# Brake_SCH.net
KiCad netlist of a schematic drawn in Altium Designer
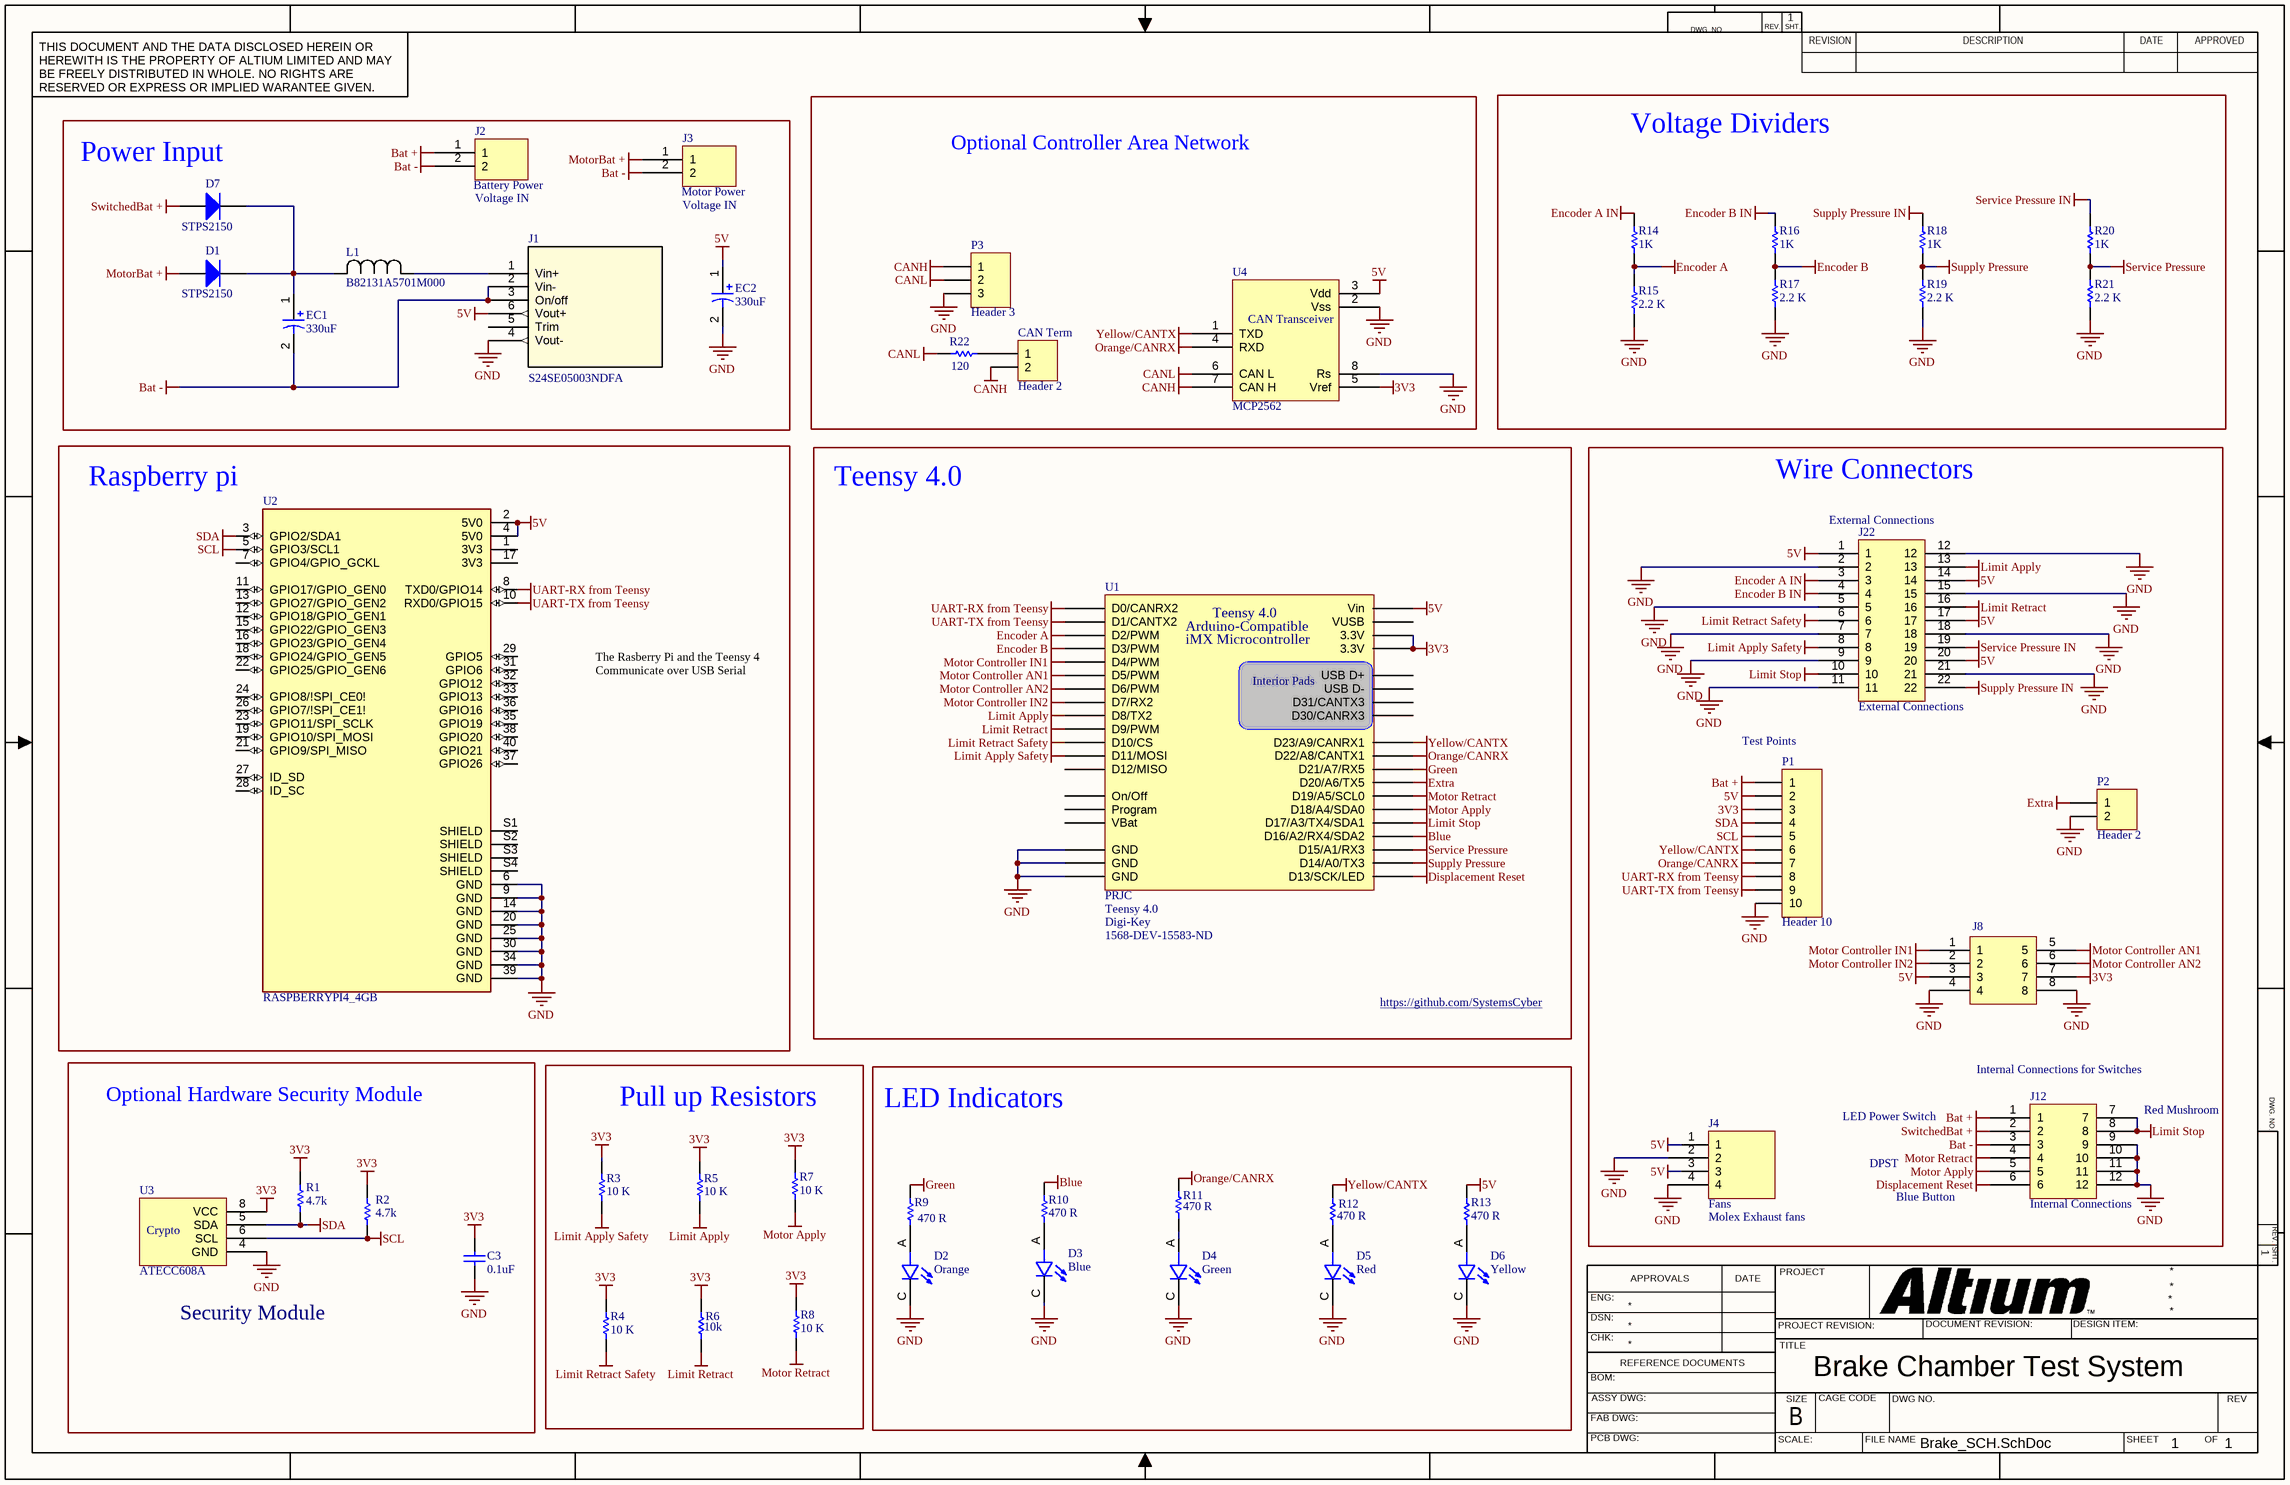
[diagram p0: Brake_SCH.SchDoc]

(export (version "E")
  (design (tool "Eeschema 10.0.6"))
  (components
    (comp (ref "C3")
      (value "0.1uF")
      (footprint "CAPR5-4X5")
      (description "Capacitor")
      (libsource (lib "Miscellaneous Devices") (part "Cap"))
    )
    (comp (ref "CAN Term")
      (value "Header 2")
      (footprint "HDR1X2")
      (description "Header, 2-Pin")
      (fields (field (name "PUBLISHER") "Altium Limited"))
      (libsource (lib "Miscellaneous Connectors") (part "Header 2"))
    )
    (comp (ref "D1")
      (value "STPS2150")
      (footprint "DO-201AD")
      (description "DIODE SCHOTTKY 150V 2A DO15")
      (libsource (lib "Miscellaneous Devices") (part "Diode 1N5408"))
    )
    (comp (ref "D2")
      (value "Orange")
      (footprint "LED_151054RS03000")
      (description "Red 623nm LED Indication - Discrete 1.9V Radial")
      (libsource (lib "151054RS03000") (part "151054RS03000"))
    )
    (comp (ref "D3")
      (value "Blue")
      (footprint "LED_151054RS03000")
      (description "Red 623nm LED Indication - Discrete 1.9V Radial")
      (libsource (lib "151054RS03000") (part "151054RS03000"))
    )
    (comp (ref "D4")
      (value "Green")
      (footprint "LED_151054RS03000")
      (description "Red 623nm LED Indication - Discrete 1.9V Radial")
      (libsource (lib "151054RS03000") (part "151054RS03000"))
    )
    (comp (ref "D5")
      (value "Red")
      (footprint "LED_151054RS03000")
      (description "Red 623nm LED Indication - Discrete 1.9V Radial")
      (libsource (lib "151054RS03000") (part "151054RS03000"))
    )
    (comp (ref "D6")
      (value "Yellow")
      (footprint "LED_151054RS03000")
      (description "Red 623nm LED Indication - Discrete 1.9V Radial")
      (libsource (lib "151054RS03000") (part "151054RS03000"))
    )
    (comp (ref "D7")
      (value "STPS2150")
      (footprint "DO-201AD")
      (description "DIODE SCHOTTKY 150V 2A DO15")
      (libsource (lib "Miscellaneous Devices") (part "Diode 1N5408"))
    )
    (comp (ref "EC1")
      (value "330uF")
      (footprint "Cap - 15mm Polarized")
      (description "CAP ALUM 220UF 20% 100V RADIAL")
      (fields (field (name "MANUFACTURER") "Nichicon") (field (name "PARTNUMBER") "UBT2A221MHD1TN"))
      (libsource (lib "Custom Parts") (part "Capacitor, Polarized"))
    )
    (comp (ref "EC2")
      (value "330uF")
      (footprint "Cap - 15mm Polarized")
      (description "CAP ALUM 220UF 20% 100V RADIAL")
      (fields (field (name "MANUFACTURER") "Nichicon") (field (name "PARTNUMBER") "UBT2A221MHD1TN"))
      (libsource (lib "Custom Parts") (part "Capacitor, Polarized"))
    )
    (comp (ref "J1")
      (value "S24SE05003NDFA")
      (footprint "CONN6_3NDFA_DEA")
      (description "No Description Available")
      (libsource (lib "S24SE05003NDFA") (part "S24SE05003NDFA"))
    )
    (comp (ref "J2")
      (value "Battery Power")
      (footprint "2 pos Mini-Fit Jr. R/A Header")
      (fields (field (name "PARTNUMBER") "39-30-1020") (field (name "MANUFACTURER") "Voltage IN"))
      (libsource (lib "Molex Mini-Fit Jr") (part "2 Pos Header"))
    )
    (comp (ref "J3")
      (value "Motor Power")
      (footprint "2 pos Mini-Fit Jr. R/A Header")
      (fields (field (name "PARTNUMBER") "39-30-1020") (field (name "MANUFACTURER") "Voltage IN"))
      (libsource (lib "Molex Mini-Fit Jr") (part "2 Pos Header"))
    )
    (comp (ref "J4")
      (value "Fans")
      (footprint "4 POS MINI-FIT JR")
      (description "CONN HEADER 4POS 4.2MM VERT TIN")
      (fields (field (name "PARTNUMBER") "39-29-9040") (field (name "MANUFACTURER") "Molex Exhaust fans"))
      (libsource (lib "Molex Mini-Fit Jr") (part "4 Pos Header Vert"))
    )
    (comp (ref "J8")
      (value "Motor Controller")
      (footprint "8 pos Mini-Fit Jr. R/A Header")
      (description "CONN HEADER 8POS 4.2MM R/A TIN")
      (fields (field (name "PARTNUMBER") "39-30-1080") (field (name "MANUFACTURER") "Molex"))
      (libsource (lib "Molex Mini-Fit Jr") (part "8 Pos Header"))
    )
    (comp (ref "J12")
      (value "Internal Connections")
      (footprint "12 pos Mini-Fit Jr. R/A Header")
      (fields (field (name "MANUFACTURER") "Molex") (field (name "PARTNUMBER") "39-30-1120"))
      (libsource (lib "Molex Mini-Fit Jr") (part "12 Pos Header"))
    )
    (comp (ref "J22")
      (value "External Connections")
      (footprint "22 pos Mini-Fit Jr. R/A Header")
      (fields (field (name "MANUFACTURER") "Molex") (field (name "PARTNUMBER") "39-30-1220"))
      (libsource (lib "Molex Mini-Fit Jr") (part "22 Pos Header"))
    )
    (comp (ref "L1")
      (value "B82131A5701M000")
      (footprint "AXIAL-0.8")
      (description "14 µH Unshielded Drum Core, Wirewound Inductor 700 mA 760mOhm Axial")
      (fields (field (name "PARTNUMBER") "8230-20-RC"))
      (libsource (lib "8230-20-RC") (part "8230-20-RC"))
    )
    (comp (ref "P1")
      (value "Header 10")
      (footprint "HDR1X10")
      (description "Header, 10-Pin")
      (fields (field (name "PUBLISHER") "Altium Limited"))
      (libsource (lib "Miscellaneous Connectors") (part "Header 10"))
    )
    (comp (ref "P2")
      (value "Header 2")
      (footprint "HDR1X2")
      (description "Header, 2-Pin")
      (libsource (lib "Miscellaneous Connectors") (part "Header 2"))
    )
    (comp (ref "P3")
      (value "Header 3")
      (footprint "HDR1X3")
      (description "Header, 3-Pin")
      (fields (field (name "PUBLISHER") "Altium Limited"))
      (libsource (lib "Miscellaneous Connectors") (part "Header 3"))
    )
    (comp (ref "R1")
      (value "4.7k")
      (footprint "AXIAL-0.4")
      (description "Resistor")
      (libsource (lib "Miscellaneous Devices") (part "Res1"))
    )
    (comp (ref "R2")
      (value "4.7k")
      (footprint "AXIAL-0.4")
      (description "Resistor")
      (libsource (lib "Miscellaneous Devices") (part "Res1"))
    )
    (comp (ref "R3")
      (value "10 K")
      (footprint "AXIAL-0.4")
      (description "Resistor")
      (fields (field (name "Comment") "10k"))
      (libsource (lib "Miscellaneous Devices") (part "Res1"))
    )
    (comp (ref "R4")
      (value "10 K")
      (footprint "AXIAL-0.4")
      (description "Resistor")
      (fields (field (name "Comment") "10k"))
      (libsource (lib "Miscellaneous Devices") (part "Res1"))
    )
    (comp (ref "R5")
      (value "10 K")
      (footprint "AXIAL-0.4")
      (description "Resistor")
      (fields (field (name "Comment") "10k"))
      (libsource (lib "Miscellaneous Devices") (part "Res1"))
    )
    (comp (ref "R6")
      (value "10k")
      (footprint "AXIAL-0.4")
      (description "Resistor")
      (libsource (lib "Miscellaneous Devices") (part "Res1"))
    )
    (comp (ref "R7")
      (value "10 K")
      (footprint "AXIAL-0.4")
      (description "Resistor")
      (fields (field (name "Comment") "10k"))
      (libsource (lib "Miscellaneous Devices") (part "Res1"))
    )
    (comp (ref "R8")
      (value "10 K")
      (footprint "AXIAL-0.4")
      (description "Resistor")
      (fields (field (name "Comment") "10k"))
      (libsource (lib "Miscellaneous Devices") (part "Res1"))
    )
    (comp (ref "R9")
      (value "470 R")
      (footprint "AXIAL-0.4")
      (description "Resistor")
      (fields (field (name "Comment") "470"))
      (libsource (lib "Miscellaneous Devices") (part "Res1"))
    )
    (comp (ref "R10")
      (value "470 R")
      (footprint "AXIAL-0.4")
      (description "Resistor")
      (fields (field (name "Comment") "470"))
      (libsource (lib "Miscellaneous Devices") (part "Res1"))
    )
    (comp (ref "R11")
      (value "470 R")
      (footprint "AXIAL-0.4")
      (description "Resistor")
      (fields (field (name "Comment") "470"))
      (libsource (lib "Miscellaneous Devices") (part "Res1"))
    )
    (comp (ref "R12")
      (value "470 R")
      (footprint "AXIAL-0.4")
      (description "Resistor")
      (fields (field (name "Comment") "470"))
      (libsource (lib "Miscellaneous Devices") (part "Res1"))
    )
    (comp (ref "R13")
      (value "470 R")
      (footprint "AXIAL-0.4")
      (description "Resistor")
      (fields (field (name "Comment") "470"))
      (libsource (lib "Miscellaneous Devices") (part "Res1"))
    )
    (comp (ref "R14")
      (value "1K")
      (footprint "AXIAL-0.4")
      (description "Resistor")
      (fields (field (name "Comment") "1k"))
      (libsource (lib "Miscellaneous Devices") (part "Res1"))
    )
    (comp (ref "R15")
      (value "2.2 K")
      (footprint "AXIAL-0.4")
      (description "Resistor")
      (fields (field (name "Comment") "2.2k"))
      (libsource (lib "Miscellaneous Devices") (part "Res1"))
    )
    (comp (ref "R16")
      (value "1K")
      (footprint "AXIAL-0.4")
      (description "Resistor")
      (fields (field (name "Comment") "1k"))
      (libsource (lib "Miscellaneous Devices") (part "Res1"))
    )
    (comp (ref "R17")
      (value "2.2 K")
      (footprint "AXIAL-0.4")
      (description "Resistor")
      (fields (field (name "Comment") "2.2k"))
      (libsource (lib "Miscellaneous Devices") (part "Res1"))
    )
    (comp (ref "R18")
      (value "1K")
      (footprint "AXIAL-0.4")
      (description "Resistor")
      (fields (field (name "Comment") "1k"))
      (libsource (lib "Miscellaneous Devices") (part "Res1"))
    )
    (comp (ref "R19")
      (value "2.2 K")
      (footprint "AXIAL-0.4")
      (description "Resistor")
      (fields (field (name "Comment") "2.2k"))
      (libsource (lib "Miscellaneous Devices") (part "Res1"))
    )
    (comp (ref "R20")
      (value "1K")
      (footprint "AXIAL-0.4")
      (description "Resistor")
      (fields (field (name "Comment") "1k"))
      (libsource (lib "Miscellaneous Devices") (part "Res1"))
    )
    (comp (ref "R21")
      (value "2.2 K")
      (footprint "AXIAL-0.4")
      (description "Resistor")
      (fields (field (name "Comment") "2.2k"))
      (libsource (lib "Miscellaneous Devices") (part "Res1"))
    )
    (comp (ref "R22")
      (value "120")
      (footprint "AXIAL-0.4")
      (description "Resistor")
      (libsource (lib "Miscellaneous Devices") (part "Res1"))
    )
    (comp (ref "U1")
      (value "Teensy 4.0")
      (footprint "Teensy 4.0")
      (description "32 Bit Arduino-Compatible iMX Microcontroller")
      (fields
        (field (name "MANUFACTURER") "PRJC")
        (field (name "PARTNUMBER") "Teensy 4.0")
        (field (name "SUPPLIER 1") "Digi-Key")
        (field (name "SUPPLIER PART NUMBER 1") "1568-DEV-15583-ND")
      )
      (libsource (lib "Teensy") (part "Teensy_4.0"))
    )
    (comp (ref "U2")
      (value "RASPBERRYPI4_4GB")
      (footprint "Mirrored MODULE_RASPBERRY_PI_3_MODEL_B")
      (description "BCM2711 Raspberry Pi 4 Model B 4GB - ARMÂ® CortexÂ®-A72 MPU Embedded Evaluation Board")
      (libsource (lib "RASPBERRYPI4_4GB") (part "RASPBERRYPI4_4GB"))
    )
    (comp (ref "U3")
      (value "ATECC608A")
      (footprint "SOIC-8")
      (description "Authentication Chip IC Networking and Communications 8-SOIC")
      (fields
        (field (name "MANUFACTURER") "Microchip Technology")
        (field (name "PARTNUMBER") "ATECC508A-SSHDA-T")
      )
      (libsource (lib "Custom Parts") (part "ATECC508A"))
    )
    (comp (ref "U4")
      (value "MCP2562")
      (footprint "DIP8")
      (libsource (lib "SSS Integrated Library") (part "MCP2551"))
    )
  )
  (nets
    (net (code "1") (name "3V3") (class "Default")
      (node (ref "C3") (pin "2") (pinfunction "2_2") (pintype "passive"))
      (node (ref "J8") (pin "7") (pinfunction "7_7") (pintype "passive"))
      (node (ref "P1") (pin "3") (pinfunction "3_3") (pintype "passive"))
      (node (ref "R1") (pin "2") (pinfunction "2_2") (pintype "passive"))
      (node (ref "R2") (pin "2") (pinfunction "2_2") (pintype "passive"))
      (node (ref "R3") (pin "2") (pinfunction "2_2") (pintype "passive"))
      (node (ref "R4") (pin "2") (pinfunction "2_2") (pintype "passive"))
      (node (ref "R5") (pin "2") (pinfunction "2_2") (pintype "passive"))
      (node (ref "R6") (pin "2") (pinfunction "2_2") (pintype "passive"))
      (node (ref "R7") (pin "2") (pinfunction "2_2") (pintype "passive"))
      (node (ref "R8") (pin "2") (pinfunction "2_2") (pintype "passive"))
      (node (ref "U1") (pin "3V3a") (pinfunction "3.3V_3V3a") (pintype "passive"))
      (node (ref "U1") (pin "3V3b") (pinfunction "3.3V_3V3b") (pintype "passive"))
      (node (ref "U3") (pin "8") (pinfunction "VCC_8") (pintype "passive"))
      (node (ref "U4") (pin "5") (pinfunction "Vref_5") (pintype "passive"))
    )
    (net (code "2") (name "5V") (class "Default")
      (node (ref "EC2") (pin "1") (pinfunction "1_1") (pintype "passive"))
      (node (ref "J1") (pin "6") (pinfunction "Vout+_6") (pintype "output"))
      (node (ref "J22") (pin "1") (pinfunction "1_1") (pintype "passive"))
      (node (ref "J22") (pin "14") (pinfunction "14_14") (pintype "passive"))
      (node (ref "J22") (pin "17") (pinfunction "17_17") (pintype "passive"))
      (node (ref "J22") (pin "20") (pinfunction "20_20") (pintype "passive"))
      (node (ref "J4") (pin "1") (pinfunction "1_1") (pintype "passive"))
      (node (ref "J4") (pin "3") (pinfunction "3_3") (pintype "passive"))
      (node (ref "J8") (pin "3") (pinfunction "3_3") (pintype "passive"))
      (node (ref "P1") (pin "2") (pinfunction "2_2") (pintype "passive"))
      (node (ref "R13") (pin "2") (pinfunction "2_2") (pintype "passive"))
      (node (ref "U1") (pin "Vin") (pinfunction "Vin_Vin") (pintype "passive"))
      (node (ref "U2") (pin "2") (pinfunction "5V0_2") (pintype "power_in"))
      (node (ref "U2") (pin "4") (pinfunction "5V0_4") (pintype "power_in"))
      (node (ref "U4") (pin "3") (pinfunction "Vdd_3") (pintype "passive"))
    )
    (net (code "3") (name "Bat +") (class "Default")
      (node (ref "J12") (pin "1") (pinfunction "1_1") (pintype "passive"))
      (node (ref "J2") (pin "1") (pinfunction "1_1") (pintype "passive"))
      (node (ref "P1") (pin "1") (pinfunction "1_1") (pintype "passive"))
    )
    (net (code "4") (name "Bat -") (class "Default")
      (node (ref "EC1") (pin "2") (pinfunction "2_2") (pintype "passive"))
      (node (ref "J1") (pin "2") (pinfunction "Vin-_2") (pintype "passive"))
      (node (ref "J1") (pin "3") (pinfunction "On/off_3") (pintype "passive"))
      (node (ref "J12") (pin "3") (pinfunction "3_3") (pintype "passive"))
      (node (ref "J2") (pin "2") (pinfunction "2_2") (pintype "passive"))
      (node (ref "J3") (pin "2") (pinfunction "2_2") (pintype "passive"))
    )
    (net (code "5") (name "Blue") (class "Default")
      (node (ref "R10") (pin "2") (pinfunction "2_2") (pintype "passive"))
      (node (ref "U1") (pin "16") (pinfunction "D16/A2/RX4/SDA2_16") (pintype "passive"))
    )
    (net (code "6") (name "CANH") (class "Default")
      (node (ref "CAN Term") (pin "2") (pinfunction "2_2") (pintype "passive"))
      (node (ref "P3") (pin "1") (pinfunction "1_1") (pintype "passive"))
      (node (ref "U4") (pin "7") (pinfunction "CAN_H_7") (pintype "passive"))
    )
    (net (code "7") (name "CANL") (class "Default")
      (node (ref "P3") (pin "2") (pinfunction "2_2") (pintype "passive"))
      (node (ref "R22") (pin "2") (pinfunction "2_2") (pintype "passive"))
      (node (ref "U4") (pin "6") (pinfunction "CAN_L_6") (pintype "passive"))
    )
    (net (code "8") (name "Displacement Reset") (class "Default")
      (node (ref "J12") (pin "6") (pinfunction "6_6") (pintype "passive"))
      (node (ref "U1") (pin "13") (pinfunction "D13/SCK/LED_13") (pintype "passive"))
    )
    (net (code "9") (name "Encoder A") (class "Default")
      (node (ref "R14") (pin "1") (pinfunction "1_1") (pintype "passive"))
      (node (ref "R15") (pin "2") (pinfunction "2_2") (pintype "passive"))
      (node (ref "U1") (pin "2") (pinfunction "D2/PWM_2") (pintype "passive"))
    )
    (net (code "10") (name "Encoder A IN") (class "Default")
      (node (ref "J22") (pin "3") (pinfunction "3_3") (pintype "passive"))
      (node (ref "R14") (pin "2") (pinfunction "2_2") (pintype "passive"))
    )
    (net (code "11") (name "Encoder B") (class "Default")
      (node (ref "R16") (pin "1") (pinfunction "1_1") (pintype "passive"))
      (node (ref "R17") (pin "2") (pinfunction "2_2") (pintype "passive"))
      (node (ref "U1") (pin "3") (pinfunction "D3/PWM_3") (pintype "passive"))
    )
    (net (code "12") (name "Encoder B IN") (class "Default")
      (node (ref "J22") (pin "4") (pinfunction "4_4") (pintype "passive"))
      (node (ref "R16") (pin "2") (pinfunction "2_2") (pintype "passive"))
    )
    (net (code "13") (name "Extra") (class "Default")
      (node (ref "P2") (pin "1") (pinfunction "1_1") (pintype "passive"))
      (node (ref "U1") (pin "20") (pinfunction "D20/A6/TX5_20") (pintype "passive"))
    )
    (net (code "14") (name "GND") (class "Default")
      (node (ref "C3") (pin "1") (pinfunction "1_1") (pintype "passive"))
      (node (ref "D2") (pin "C") (pinfunction "C_C") (pintype "passive"))
      (node (ref "D3") (pin "C") (pinfunction "C_C") (pintype "passive"))
      (node (ref "D4") (pin "C") (pinfunction "C_C") (pintype "passive"))
      (node (ref "D5") (pin "C") (pinfunction "C_C") (pintype "passive"))
      (node (ref "D6") (pin "C") (pinfunction "C_C") (pintype "passive"))
      (node (ref "EC2") (pin "2") (pinfunction "2_2") (pintype "passive"))
      (node (ref "J1") (pin "4") (pinfunction "Vout-_4") (pintype "output"))
      (node (ref "J12") (pin "10") (pinfunction "10_10") (pintype "passive"))
      (node (ref "J12") (pin "11") (pinfunction "11_11") (pintype "passive"))
      (node (ref "J12") (pin "12") (pinfunction "12_12") (pintype "passive"))
      (node (ref "J12") (pin "9") (pinfunction "9_9") (pintype "passive"))
      (node (ref "J22") (pin "11") (pinfunction "11_11") (pintype "passive"))
      (node (ref "J22") (pin "12") (pinfunction "12_12") (pintype "passive"))
      (node (ref "J22") (pin "15") (pinfunction "15_15") (pintype "passive"))
      (node (ref "J22") (pin "18") (pinfunction "18_18") (pintype "passive"))
      (node (ref "J22") (pin "2") (pinfunction "2_2") (pintype "passive"))
      (node (ref "J22") (pin "21") (pinfunction "21_21") (pintype "passive"))
      (node (ref "J22") (pin "5") (pinfunction "5_5") (pintype "passive"))
      (node (ref "J22") (pin "7") (pinfunction "7_7") (pintype "passive"))
      (node (ref "J22") (pin "9") (pinfunction "9_9") (pintype "passive"))
      (node (ref "J4") (pin "2") (pinfunction "2_2") (pintype "passive"))
      (node (ref "J4") (pin "4") (pinfunction "4_4") (pintype "passive"))
      (node (ref "J8") (pin "4") (pinfunction "4_4") (pintype "passive"))
      (node (ref "J8") (pin "8") (pinfunction "8_8") (pintype "passive"))
      (node (ref "P1") (pin "10") (pinfunction "10_10") (pintype "passive"))
      (node (ref "P2") (pin "2") (pinfunction "2_2") (pintype "passive"))
      (node (ref "P3") (pin "3") (pinfunction "3_3") (pintype "passive"))
      (node (ref "R15") (pin "1") (pinfunction "1_1") (pintype "passive"))
      (node (ref "R17") (pin "1") (pinfunction "1_1") (pintype "passive"))
      (node (ref "R19") (pin "1") (pinfunction "1_1") (pintype "passive"))
      (node (ref "R21") (pin "1") (pinfunction "1_1") (pintype "passive"))
      (node (ref "U1") (pin "G1") (pinfunction "GND_G1") (pintype "passive"))
      (node (ref "U1") (pin "G2") (pinfunction "GND_G2") (pintype "passive"))
      (node (ref "U1") (pin "G3") (pinfunction "GND_G3") (pintype "passive"))
      (node (ref "U2") (pin "14") (pinfunction "GND_14") (pintype "power_in"))
      (node (ref "U2") (pin "20") (pinfunction "GND_20") (pintype "power_in"))
      (node (ref "U2") (pin "25") (pinfunction "GND_25") (pintype "power_in"))
      (node (ref "U2") (pin "30") (pinfunction "GND_30") (pintype "power_in"))
      (node (ref "U2") (pin "34") (pinfunction "GND_34") (pintype "power_in"))
      (node (ref "U2") (pin "39") (pinfunction "GND_39") (pintype "power_in"))
      (node (ref "U2") (pin "6") (pinfunction "GND_6") (pintype "power_in"))
      (node (ref "U2") (pin "9") (pinfunction "GND_9") (pintype "power_in"))
      (node (ref "U3") (pin "4") (pinfunction "GND_4") (pintype "passive"))
      (node (ref "U4") (pin "2") (pinfunction "Vss_2") (pintype "passive"))
      (node (ref "U4") (pin "8") (pinfunction "Rs_8") (pintype "passive"))
    )
    (net (code "15") (name "Green") (class "Default")
      (node (ref "R9") (pin "2") (pinfunction "2_2") (pintype "passive"))
      (node (ref "U1") (pin "21") (pinfunction "D21/A7/RX5_21") (pintype "passive"))
    )
    (net (code "16") (name "Limit Apply") (class "Default")
      (node (ref "J22") (pin "13") (pinfunction "13_13") (pintype "passive"))
      (node (ref "R5") (pin "1") (pinfunction "1_1") (pintype "passive"))
      (node (ref "U1") (pin "8") (pinfunction "D8/TX2_8") (pintype "passive"))
    )
    (net (code "17") (name "Limit Apply Safety") (class "Default")
      (node (ref "J22") (pin "8") (pinfunction "8_8") (pintype "passive"))
      (node (ref "R3") (pin "1") (pinfunction "1_1") (pintype "passive"))
      (node (ref "U1") (pin "11") (pinfunction "D11/MOSI_11") (pintype "passive"))
    )
    (net (code "18") (name "Limit Retract") (class "Default")
      (node (ref "J22") (pin "16") (pinfunction "16_16") (pintype "passive"))
      (node (ref "R6") (pin "1") (pinfunction "1_1") (pintype "passive"))
      (node (ref "U1") (pin "9") (pinfunction "D9/PWM_9") (pintype "passive"))
    )
    (net (code "19") (name "Limit Retract Safety") (class "Default")
      (node (ref "J22") (pin "6") (pinfunction "6_6") (pintype "passive"))
      (node (ref "R4") (pin "1") (pinfunction "1_1") (pintype "passive"))
      (node (ref "U1") (pin "10") (pinfunction "D10/CS_10") (pintype "passive"))
    )
    (net (code "20") (name "Limit Stop") (class "Default")
      (node (ref "J12") (pin "7") (pinfunction "7_7") (pintype "passive"))
      (node (ref "J12") (pin "8") (pinfunction "8_8") (pintype "passive"))
      (node (ref "J22") (pin "10") (pinfunction "10_10") (pintype "passive"))
      (node (ref "U1") (pin "17") (pinfunction "D17/A3/TX4/SDA1_17") (pintype "passive"))
    )
    (net (code "21") (name "Motor Apply") (class "Default")
      (node (ref "J12") (pin "5") (pinfunction "5_5") (pintype "passive"))
      (node (ref "R7") (pin "1") (pinfunction "1_1") (pintype "passive"))
      (node (ref "U1") (pin "18") (pinfunction "D18/A4/SDA0_18") (pintype "passive"))
    )
    (net (code "22") (name "Motor Controller AN1") (class "Default")
      (node (ref "J8") (pin "5") (pinfunction "5_5") (pintype "passive"))
      (node (ref "U1") (pin "5") (pinfunction "D5/PWM_5") (pintype "passive"))
    )
    (net (code "23") (name "Motor Controller AN2") (class "Default")
      (node (ref "J8") (pin "6") (pinfunction "6_6") (pintype "passive"))
      (node (ref "U1") (pin "6") (pinfunction "D6/PWM_6") (pintype "passive"))
    )
    (net (code "24") (name "Motor Controller IN1") (class "Default")
      (node (ref "J8") (pin "1") (pinfunction "1_1") (pintype "passive"))
      (node (ref "U1") (pin "4") (pinfunction "D4/PWM_4") (pintype "passive"))
    )
    (net (code "25") (name "Motor Controller IN2") (class "Default")
      (node (ref "J8") (pin "2") (pinfunction "2_2") (pintype "passive"))
      (node (ref "U1") (pin "7") (pinfunction "D7/RX2_7") (pintype "passive"))
    )
    (net (code "26") (name "Motor Retract") (class "Default")
      (node (ref "J12") (pin "4") (pinfunction "4_4") (pintype "passive"))
      (node (ref "R8") (pin "1") (pinfunction "1_1") (pintype "passive"))
      (node (ref "U1") (pin "19") (pinfunction "D19/A5/SCL0_19") (pintype "passive"))
    )
    (net (code "27") (name "MotorBat +") (class "Default")
      (node (ref "D1") (pin "1") (pinfunction "A_1") (pintype "passive"))
      (node (ref "J3") (pin "1") (pinfunction "1_1") (pintype "passive"))
    )
    (net (code "28") (name "Net-(CAN Term-Pad1)") (class "Default")
      (node (ref "CAN Term") (pin "1") (pinfunction "1_1") (pintype "passive"))
      (node (ref "R22") (pin "1") (pinfunction "1_1") (pintype "passive"))
    )
    (net (code "29") (name "Net-(D1-K)") (class "Default")
      (node (ref "D1") (pin "2") (pinfunction "K_2") (pintype "passive"))
      (node (ref "D7") (pin "2") (pinfunction "K_2") (pintype "passive"))
      (node (ref "EC1") (pin "1") (pinfunction "1_1") (pintype "passive"))
      (node (ref "L1") (pin "2") (pinfunction "2_2") (pintype "passive"))
    )
    (net (code "30") (name "Net-(D2-PadA)") (class "Default")
      (node (ref "D2") (pin "A") (pinfunction "A_A") (pintype "passive"))
      (node (ref "R9") (pin "1") (pinfunction "1_1") (pintype "passive"))
    )
    (net (code "31") (name "Net-(D3-PadA)") (class "Default")
      (node (ref "D3") (pin "A") (pinfunction "A_A") (pintype "passive"))
      (node (ref "R10") (pin "1") (pinfunction "1_1") (pintype "passive"))
    )
    (net (code "32") (name "Net-(D4-PadA)") (class "Default")
      (node (ref "D4") (pin "A") (pinfunction "A_A") (pintype "passive"))
      (node (ref "R11") (pin "1") (pinfunction "1_1") (pintype "passive"))
    )
    (net (code "33") (name "Net-(D5-PadA)") (class "Default")
      (node (ref "D5") (pin "A") (pinfunction "A_A") (pintype "passive"))
      (node (ref "R12") (pin "1") (pinfunction "1_1") (pintype "passive"))
    )
    (net (code "34") (name "Net-(D6-PadA)") (class "Default")
      (node (ref "D6") (pin "A") (pinfunction "A_A") (pintype "passive"))
      (node (ref "R13") (pin "1") (pinfunction "1_1") (pintype "passive"))
    )
    (net (code "35") (name "Net-(J1-Vin+)") (class "Default")
      (node (ref "J1") (pin "1") (pinfunction "Vin+_1") (pintype "passive"))
      (node (ref "L1") (pin "1") (pinfunction "1_1") (pintype "passive"))
    )
    (net (code "36") (name "Orange{slash}CANRX") (class "Default")
      (node (ref "P1") (pin "7") (pinfunction "7_7") (pintype "passive"))
      (node (ref "R11") (pin "2") (pinfunction "2_2") (pintype "passive"))
      (node (ref "U1") (pin "22") (pinfunction "D22/A8/CANTX1_22") (pintype "passive"))
      (node (ref "U4") (pin "4") (pinfunction "RXD_4") (pintype "passive"))
    )
    (net (code "37") (name "SCL") (class "Default")
      (node (ref "P1") (pin "5") (pinfunction "5_5") (pintype "passive"))
      (node (ref "R2") (pin "1") (pinfunction "1_1") (pintype "passive"))
      (node (ref "U2") (pin "5") (pinfunction "GPIO3/SCL1_5") (pintype "bidirectional"))
      (node (ref "U3") (pin "6") (pinfunction "SCL_6") (pintype "passive"))
    )
    (net (code "38") (name "SDA") (class "Default")
      (node (ref "P1") (pin "4") (pinfunction "4_4") (pintype "passive"))
      (node (ref "R1") (pin "1") (pinfunction "1_1") (pintype "passive"))
      (node (ref "U2") (pin "3") (pinfunction "GPIO2/SDA1_3") (pintype "bidirectional"))
      (node (ref "U3") (pin "5") (pinfunction "SDA_5") (pintype "passive"))
    )
    (net (code "39") (name "Service Pressure") (class "Default")
      (node (ref "R20") (pin "1") (pinfunction "1_1") (pintype "passive"))
      (node (ref "R21") (pin "2") (pinfunction "2_2") (pintype "passive"))
      (node (ref "U1") (pin "15") (pinfunction "D15/A1/RX3_15") (pintype "passive"))
    )
    (net (code "40") (name "Service Pressure IN") (class "Default")
      (node (ref "J22") (pin "19") (pinfunction "19_19") (pintype "passive"))
      (node (ref "R20") (pin "2") (pinfunction "2_2") (pintype "passive"))
    )
    (net (code "41") (name "Supply Pressure") (class "Default")
      (node (ref "R18") (pin "1") (pinfunction "1_1") (pintype "passive"))
      (node (ref "R19") (pin "2") (pinfunction "2_2") (pintype "passive"))
      (node (ref "U1") (pin "14") (pinfunction "D14/A0/TX3_14") (pintype "passive"))
    )
    (net (code "42") (name "Supply Pressure IN") (class "Default")
      (node (ref "J22") (pin "22") (pinfunction "22_22") (pintype "passive"))
      (node (ref "R18") (pin "2") (pinfunction "2_2") (pintype "passive"))
    )
    (net (code "43") (name "SwitchedBat +") (class "Default")
      (node (ref "D7") (pin "1") (pinfunction "A_1") (pintype "passive"))
      (node (ref "J12") (pin "2") (pinfunction "2_2") (pintype "passive"))
    )
    (net (code "44") (name "UART-RX from Teensy") (class "Default")
      (node (ref "P1") (pin "8") (pinfunction "8_8") (pintype "passive"))
      (node (ref "U1") (pin "0") (pinfunction "D0/CANRX2_0") (pintype "passive"))
      (node (ref "U2") (pin "8") (pinfunction "TXD0/GPIO14_8") (pintype "bidirectional"))
    )
    (net (code "45") (name "UART-TX from Teensy") (class "Default")
      (node (ref "P1") (pin "9") (pinfunction "9_9") (pintype "passive"))
      (node (ref "U1") (pin "1") (pinfunction "D1/CANTX2_1") (pintype "passive"))
      (node (ref "U2") (pin "10") (pinfunction "RXD0/GPIO15_10") (pintype "bidirectional"))
    )
    (net (code "46") (name "Yellow{slash}CANTX") (class "Default")
      (node (ref "P1") (pin "6") (pinfunction "6_6") (pintype "passive"))
      (node (ref "R12") (pin "2") (pinfunction "2_2") (pintype "passive"))
      (node (ref "U1") (pin "23") (pinfunction "D23/A9/CANRX1_23") (pintype "passive"))
      (node (ref "U4") (pin "1") (pinfunction "TXD_1") (pintype "passive"))
    )
    (net (code "47") (name "unconnected-(J1-Trim-Pad5)") (class "Default")
      (node (ref "J1") (pin "5") (pinfunction "Trim_5") (pintype "passive"))
    )
    (net (code "48") (name "unconnected-(U1-D12{slash}MISO-Pad12)") (class "Default")
      (node (ref "U1") (pin "12") (pinfunction "D12/MISO_12") (pintype "passive"))
    )
    (net (code "49") (name "unconnected-(U1-D30{slash}CANRX3-PadCRX3)") (class "Default")
      (node (ref "U1") (pin "CRX3") (pinfunction "D30/CANRX3_CRX3") (pintype "passive"))
    )
    (net (code "50") (name "unconnected-(U1-D31{slash}CANTX3-PadCTX3)") (class "Default")
      (node (ref "U1") (pin "CTX3") (pinfunction "D31/CANTX3_CTX3") (pintype "passive"))
    )
    (net (code "51") (name "unconnected-(U1-On{slash}Off-PadOn)") (class "Default")
      (node (ref "U1") (pin "On") (pinfunction "On/Off_On") (pintype "passive"))
    )
    (net (code "52") (name "unconnected-(U1-PadVBat)") (class "Default")
      (node (ref "U1") (pin "VBat") (pinfunction "VBat_VBat") (pintype "passive"))
    )
    (net (code "53") (name "unconnected-(U1-PadVUSB)") (class "Default")
      (node (ref "U1") (pin "VUSB") (pinfunction "VUSB_VUSB") (pintype "passive"))
    )
    (net (code "54") (name "unconnected-(U1-Program-PadP)") (class "Default")
      (node (ref "U1") (pin "P") (pinfunction "Program_P") (pintype "passive"))
    )
    (net (code "55") (name "unconnected-(U1-USB_D+-PadD+)") (class "Default")
      (node (ref "U1") (pin "D+") (pinfunction "USB_D+_D+") (pintype "passive"))
    )
    (net (code "56") (name "unconnected-(U1-USB_D--PadD-)") (class "Default")
      (node (ref "U1") (pin "D-") (pinfunction "USB_D-_D-") (pintype "passive"))
    )
    (net (code "57") (name "unconnected-(U2-3V3-Pad1)") (class "Default")
      (node (ref "U2") (pin "1") (pinfunction "3V3_1") (pintype "power_in"))
    )
    (net (code "58") (name "unconnected-(U2-3V3-Pad17)") (class "Default")
      (node (ref "U2") (pin "17") (pinfunction "3V3_17") (pintype "power_in"))
    )
    (net (code "59") (name "unconnected-(U2-GPIO4{slash}GPIO_GCKL-Pad7)") (class "Default")
      (node (ref "U2") (pin "7") (pinfunction "GPIO4/GPIO_GCKL_7") (pintype "bidirectional"))
    )
    (net (code "60") (name "unconnected-(U2-GPIO5-Pad29)") (class "Default")
      (node (ref "U2") (pin "29") (pinfunction "GPIO5_29") (pintype "bidirectional"))
    )
    (net (code "61") (name "unconnected-(U2-GPIO6-Pad31)") (class "Default")
      (node (ref "U2") (pin "31") (pinfunction "GPIO6_31") (pintype "bidirectional"))
    )
    (net (code "62") (name "unconnected-(U2-GPIO7{slash}!SPI_CE1!-Pad26)") (class "Default")
      (node (ref "U2") (pin "26") (pinfunction "GPIO7/!SPI_CE1!_26") (pintype "bidirectional"))
    )
    (net (code "63") (name "unconnected-(U2-GPIO8{slash}!SPI_CE0!-Pad24)") (class "Default")
      (node (ref "U2") (pin "24") (pinfunction "GPIO8/!SPI_CE0!_24") (pintype "bidirectional"))
    )
    (net (code "64") (name "unconnected-(U2-GPIO9{slash}SPI_MISO-Pad21)") (class "Default")
      (node (ref "U2") (pin "21") (pinfunction "GPIO9/SPI_MISO_21") (pintype "bidirectional"))
    )
    (net (code "65") (name "unconnected-(U2-GPIO10{slash}SPI_MOSI-Pad19)") (class "Default")
      (node (ref "U2") (pin "19") (pinfunction "GPIO10/SPI_MOSI_19") (pintype "bidirectional"))
    )
    (net (code "66") (name "unconnected-(U2-GPIO11{slash}SPI_SCLK-Pad23)") (class "Default")
      (node (ref "U2") (pin "23") (pinfunction "GPIO11/SPI_SCLK_23") (pintype "bidirectional"))
    )
    (net (code "67") (name "unconnected-(U2-GPIO12-Pad32)") (class "Default")
      (node (ref "U2") (pin "32") (pinfunction "GPIO12_32") (pintype "bidirectional"))
    )
    (net (code "68") (name "unconnected-(U2-GPIO13-Pad33)") (class "Default")
      (node (ref "U2") (pin "33") (pinfunction "GPIO13_33") (pintype "bidirectional"))
    )
    (net (code "69") (name "unconnected-(U2-GPIO16-Pad36)") (class "Default")
      (node (ref "U2") (pin "36") (pinfunction "GPIO16_36") (pintype "bidirectional"))
    )
    (net (code "70") (name "unconnected-(U2-GPIO17{slash}GPIO_GEN0-Pad11)") (class "Default")
      (node (ref "U2") (pin "11") (pinfunction "GPIO17/GPIO_GEN0_11") (pintype "bidirectional"))
    )
    (net (code "71") (name "unconnected-(U2-GPIO18{slash}GPIO_GEN1-Pad12)") (class "Default")
      (node (ref "U2") (pin "12") (pinfunction "GPIO18/GPIO_GEN1_12") (pintype "bidirectional"))
    )
    (net (code "72") (name "unconnected-(U2-GPIO19-Pad35)") (class "Default")
      (node (ref "U2") (pin "35") (pinfunction "GPIO19_35") (pintype "bidirectional"))
    )
    (net (code "73") (name "unconnected-(U2-GPIO20-Pad38)") (class "Default")
      (node (ref "U2") (pin "38") (pinfunction "GPIO20_38") (pintype "bidirectional"))
    )
    (net (code "74") (name "unconnected-(U2-GPIO21-Pad40)") (class "Default")
      (node (ref "U2") (pin "40") (pinfunction "GPIO21_40") (pintype "bidirectional"))
    )
    (net (code "75") (name "unconnected-(U2-GPIO22{slash}GPIO_GEN3-Pad15)") (class "Default")
      (node (ref "U2") (pin "15") (pinfunction "GPIO22/GPIO_GEN3_15") (pintype "bidirectional"))
    )
    (net (code "76") (name "unconnected-(U2-GPIO23{slash}GPIO_GEN4-Pad16)") (class "Default")
      (node (ref "U2") (pin "16") (pinfunction "GPIO23/GPIO_GEN4_16") (pintype "bidirectional"))
    )
    (net (code "77") (name "unconnected-(U2-GPIO24{slash}GPIO_GEN5-Pad18)") (class "Default")
      (node (ref "U2") (pin "18") (pinfunction "GPIO24/GPIO_GEN5_18") (pintype "bidirectional"))
    )
    (net (code "78") (name "unconnected-(U2-GPIO25{slash}GPIO_GEN6-Pad22)") (class "Default")
      (node (ref "U2") (pin "22") (pinfunction "GPIO25/GPIO_GEN6_22") (pintype "bidirectional"))
    )
    (net (code "79") (name "unconnected-(U2-GPIO26-Pad37)") (class "Default")
      (node (ref "U2") (pin "37") (pinfunction "GPIO26_37") (pintype "bidirectional"))
    )
    (net (code "80") (name "unconnected-(U2-GPIO27{slash}GPIO_GEN2-Pad13)") (class "Default")
      (node (ref "U2") (pin "13") (pinfunction "GPIO27/GPIO_GEN2_13") (pintype "bidirectional"))
    )
    (net (code "81") (name "unconnected-(U2-ID_SC-Pad28)") (class "Default")
      (node (ref "U2") (pin "28") (pinfunction "ID_SC_28") (pintype "bidirectional"))
    )
    (net (code "82") (name "unconnected-(U2-ID_SD-Pad27)") (class "Default")
      (node (ref "U2") (pin "27") (pinfunction "ID_SD_27") (pintype "bidirectional"))
    )
    (net (code "83") (name "unconnected-(U2-SHIELD-PadS1)") (class "Default")
      (node (ref "U2") (pin "S1") (pinfunction "SHIELD_S1") (pintype "power_in"))
    )
    (net (code "84") (name "unconnected-(U2-SHIELD-PadS2)") (class "Default")
      (node (ref "U2") (pin "S2") (pinfunction "SHIELD_S2") (pintype "power_in"))
    )
    (net (code "85") (name "unconnected-(U2-SHIELD-PadS3)") (class "Default")
      (node (ref "U2") (pin "S3") (pinfunction "SHIELD_S3") (pintype "power_in"))
    )
    (net (code "86") (name "unconnected-(U2-SHIELD-PadS4)") (class "Default")
      (node (ref "U2") (pin "S4") (pinfunction "SHIELD_S4") (pintype "power_in"))
    )
  )
)
